# fpc.net
KiCad netlist of a schematic drawn in Altium Designer
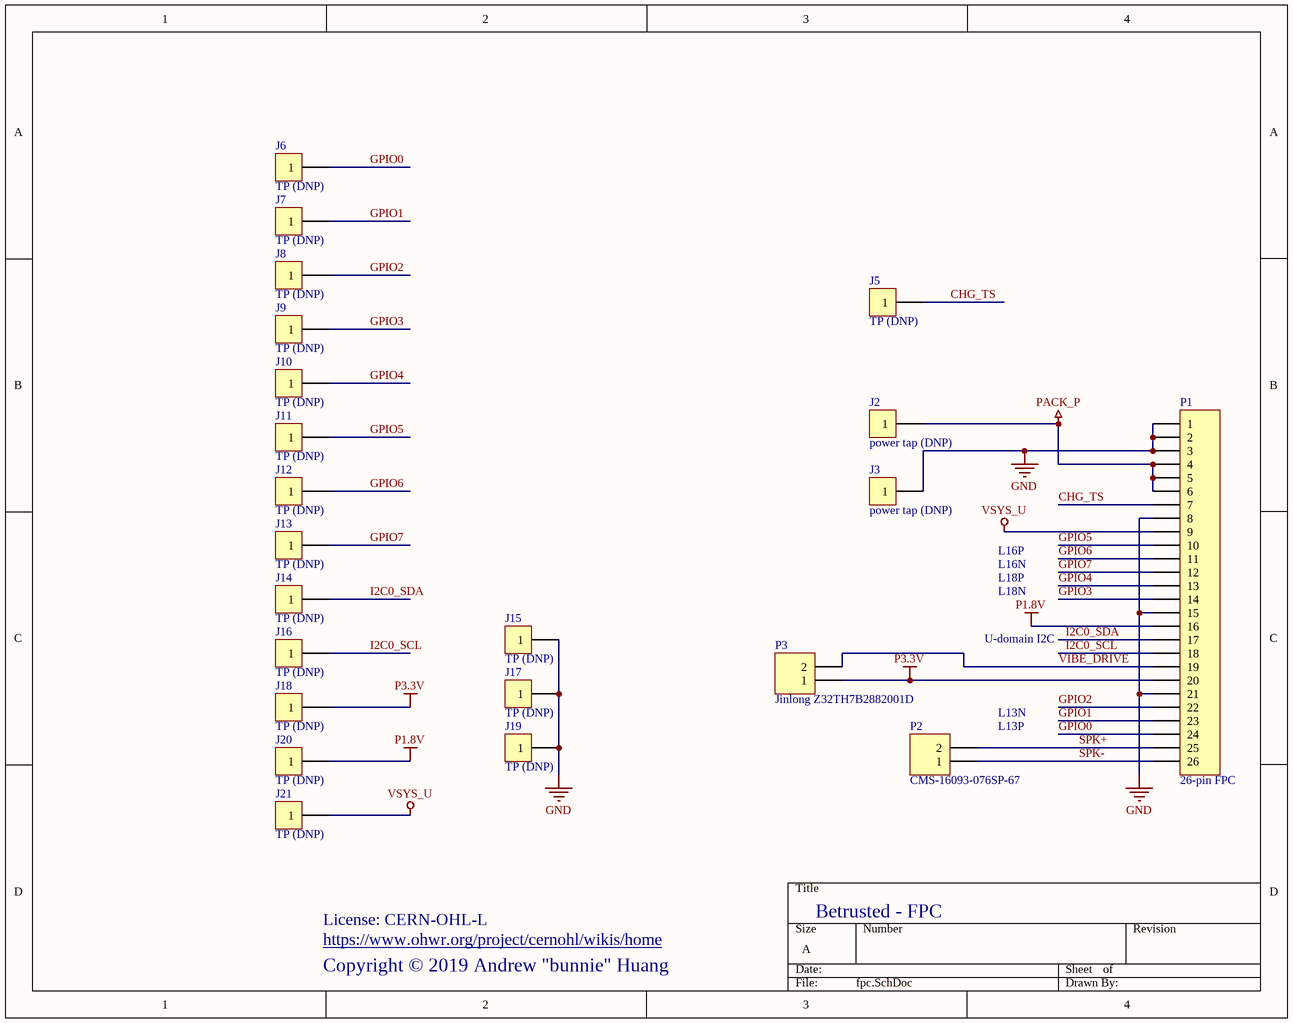
[diagram p0: fpc.SchDoc]

(export (version "E")
  (design (tool "Eeschema 10.0.6"))
  (components
    (comp (ref "J2")
      (value "power tap (DNP)")
      (footprint "RESTAP-0603")
      (description "Connector")
      (fields (field (name "MPN") "DNP"))
      (libsource (lib "*") (part "CON1"))
    )
    (comp (ref "J3")
      (value "power tap (DNP)")
      (footprint "RESTAP-0603")
      (description "Connector")
      (fields (field (name "MPN") "DNP"))
      (libsource (lib "*") (part "CON1"))
    )
    (comp (ref "J5")
      (value "TP (DNP)")
      (footprint "TP_1.5x1_SMT")
      (description "Connector")
      (fields (field (name "MPN") "DNP"))
      (libsource (lib "*") (part "CON1"))
    )
    (comp (ref "J6")
      (value "TP (DNP)")
      (footprint "TP_1.5x1_SMT")
      (description "Connector")
      (fields (field (name "MPN") "DNP"))
      (libsource (lib "*") (part "CON1"))
    )
    (comp (ref "J7")
      (value "TP (DNP)")
      (footprint "TP_1.5x1_SMT")
      (description "Connector")
      (fields (field (name "MPN") "DNP"))
      (libsource (lib "*") (part "CON1"))
    )
    (comp (ref "J8")
      (value "TP (DNP)")
      (footprint "TP_1.5x1_SMT")
      (description "Connector")
      (fields (field (name "MPN") "DNP"))
      (libsource (lib "*") (part "CON1"))
    )
    (comp (ref "J9")
      (value "TP (DNP)")
      (footprint "TP_1.5x1_SMT")
      (description "Connector")
      (fields (field (name "MPN") "DNP"))
      (libsource (lib "*") (part "CON1"))
    )
    (comp (ref "J10")
      (value "TP (DNP)")
      (footprint "TP_1.5x1_SMT")
      (description "Connector")
      (fields (field (name "MPN") "DNP"))
      (libsource (lib "*") (part "CON1"))
    )
    (comp (ref "J11")
      (value "TP (DNP)")
      (footprint "TP_1.5x1_SMT")
      (description "Connector")
      (fields (field (name "MPN") "DNP"))
      (libsource (lib "*") (part "CON1"))
    )
    (comp (ref "J12")
      (value "TP (DNP)")
      (footprint "TP_1.5x1_SMT")
      (description "Connector")
      (fields (field (name "MPN") "DNP"))
      (libsource (lib "*") (part "CON1"))
    )
    (comp (ref "J13")
      (value "TP (DNP)")
      (footprint "TP_1.5x1_SMT")
      (description "Connector")
      (fields (field (name "MPN") "DNP"))
      (libsource (lib "*") (part "CON1"))
    )
    (comp (ref "J14")
      (value "TP (DNP)")
      (footprint "TP_1.5x1_SMT")
      (description "Connector")
      (fields (field (name "MPN") "DNP"))
      (libsource (lib "*") (part "CON1"))
    )
    (comp (ref "J15")
      (value "TP (DNP)")
      (footprint "TP_1.5x1_SMT")
      (description "Connector")
      (fields (field (name "MPN") "DNP"))
      (libsource (lib "*") (part "CON1"))
    )
    (comp (ref "J16")
      (value "TP (DNP)")
      (footprint "TP_1.5x1_SMT")
      (description "Connector")
      (fields (field (name "MPN") "DNP"))
      (libsource (lib "*") (part "CON1"))
    )
    (comp (ref "J17")
      (value "TP (DNP)")
      (footprint "TP_1.5x1_SMT")
      (description "Connector")
      (fields (field (name "MPN") "DNP"))
      (libsource (lib "*") (part "CON1"))
    )
    (comp (ref "J18")
      (value "TP (DNP)")
      (footprint "TP_1.5x1_SMT")
      (description "Connector")
      (fields (field (name "MPN") "DNP"))
      (libsource (lib "*") (part "CON1"))
    )
    (comp (ref "J19")
      (value "TP (DNP)")
      (footprint "TP_1.5x1_SMT")
      (description "Connector")
      (fields (field (name "MPN") "DNP"))
      (libsource (lib "*") (part "CON1"))
    )
    (comp (ref "J20")
      (value "TP (DNP)")
      (footprint "TP_1.5x1_SMT")
      (description "Connector")
      (fields (field (name "MPN") "DNP"))
      (libsource (lib "*") (part "CON1"))
    )
    (comp (ref "J21")
      (value "TP (DNP)")
      (footprint "TP_1.5x1_SMT")
      (description "Connector")
      (fields (field (name "MPN") "DNP"))
      (libsource (lib "*") (part "CON1"))
    )
    (comp (ref "P1")
      (value "26-pin FPC")
      (footprint "HRS_FH34SRJ-26S-FPC-TOP")
      (description "26 Pin FPC footprint")
      (fields (field (name "MPN") "DNP"))
      (libsource (lib "commonsch-new") (part "FPC-26"))
    )
    (comp (ref "P2")
      (value "CMS-16093-076SP-67")
      (footprint "CUI_CMS-16093-076SP-67")
      (fields (field (name "PUBLISHER") "Altium Limited"))
      (libsource (lib "Miscellaneous Connectors") (part "Header 2"))
    )
    (comp (ref "P3")
      (value "Jinlong Z32TH7B2882001D")
      (footprint "JINLONG_Z32TH7B2882001D")
      (fields (field (name "MPN") "Z32TH7B2882001D") (field (name "PUBLISHER") "Altium Limited"))
      (libsource (lib "Miscellaneous Connectors") (part "Header 2"))
    )
  )
  (nets
    (net (code "1") (name "/CHG_TS") (class "Default")
      (node (ref "J5") (pin "1") (pinfunction "1_1") (pintype "passive"))
      (node (ref "P1") (pin "7") (pinfunction "7_7") (pintype "passive"))
    )
    (net (code "2") (name "/GPIO0") (class "Default")
      (node (ref "J6") (pin "1") (pinfunction "1_1") (pintype "passive"))
      (node (ref "P1") (pin "24") (pinfunction "24_24") (pintype "passive"))
    )
    (net (code "3") (name "/GPIO1") (class "Default")
      (node (ref "J7") (pin "1") (pinfunction "1_1") (pintype "passive"))
      (node (ref "P1") (pin "23") (pinfunction "23_23") (pintype "passive"))
    )
    (net (code "4") (name "/GPIO2") (class "Default")
      (node (ref "J8") (pin "1") (pinfunction "1_1") (pintype "passive"))
      (node (ref "P1") (pin "22") (pinfunction "22_22") (pintype "passive"))
    )
    (net (code "5") (name "/GPIO3") (class "Default")
      (node (ref "J9") (pin "1") (pinfunction "1_1") (pintype "passive"))
      (node (ref "P1") (pin "14") (pinfunction "14_14") (pintype "passive"))
    )
    (net (code "6") (name "/GPIO4") (class "Default")
      (node (ref "J10") (pin "1") (pinfunction "1_1") (pintype "passive"))
      (node (ref "P1") (pin "13") (pinfunction "13_13") (pintype "passive"))
    )
    (net (code "7") (name "/GPIO5") (class "Default")
      (node (ref "J11") (pin "1") (pinfunction "1_1") (pintype "passive"))
      (node (ref "P1") (pin "10") (pinfunction "10_10") (pintype "passive"))
    )
    (net (code "8") (name "/GPIO6") (class "Default")
      (node (ref "J12") (pin "1") (pinfunction "1_1") (pintype "passive"))
      (node (ref "P1") (pin "11") (pinfunction "11_11") (pintype "passive"))
    )
    (net (code "9") (name "/GPIO7") (class "Default")
      (node (ref "J13") (pin "1") (pinfunction "1_1") (pintype "passive"))
      (node (ref "P1") (pin "12") (pinfunction "12_12") (pintype "passive"))
    )
    (net (code "10") (name "/I2C0_SCL") (class "Default")
      (node (ref "J16") (pin "1") (pinfunction "1_1") (pintype "passive"))
      (node (ref "P1") (pin "18") (pinfunction "18_18") (pintype "passive"))
    )
    (net (code "11") (name "/I2C0_SDA") (class "Default")
      (node (ref "J14") (pin "1") (pinfunction "1_1") (pintype "passive"))
      (node (ref "P1") (pin "17") (pinfunction "17_17") (pintype "passive"))
    )
    (net (code "12") (name "/SPK+") (class "Default")
      (node (ref "P1") (pin "25") (pinfunction "25_25") (pintype "passive"))
      (node (ref "P2") (pin "2") (pinfunction "2_2") (pintype "passive"))
    )
    (net (code "13") (name "/SPK-") (class "Default")
      (node (ref "P1") (pin "26") (pinfunction "26_26") (pintype "passive"))
      (node (ref "P2") (pin "1") (pinfunction "1_1") (pintype "passive"))
    )
    (net (code "14") (name "/VIBE_DRIVE") (class "Default")
      (node (ref "P1") (pin "19") (pinfunction "19_19") (pintype "passive"))
      (node (ref "P3") (pin "2") (pinfunction "2_2") (pintype "passive"))
    )
    (net (code "15") (name "GND") (class "Default")
      (node (ref "J15") (pin "1") (pinfunction "1_1") (pintype "passive"))
      (node (ref "J17") (pin "1") (pinfunction "1_1") (pintype "passive"))
      (node (ref "J19") (pin "1") (pinfunction "1_1") (pintype "passive"))
      (node (ref "J3") (pin "1") (pinfunction "1_1") (pintype "passive"))
      (node (ref "P1") (pin "1") (pinfunction "1_1") (pintype "passive"))
      (node (ref "P1") (pin "15") (pinfunction "15_15") (pintype "passive"))
      (node (ref "P1") (pin "2") (pinfunction "2_2") (pintype "passive"))
      (node (ref "P1") (pin "21") (pinfunction "21_21") (pintype "passive"))
      (node (ref "P1") (pin "3") (pinfunction "3_3") (pintype "passive"))
      (node (ref "P1") (pin "8") (pinfunction "8_8") (pintype "passive"))
    )
    (net (code "16") (name "P1.8V") (class "Default")
      (node (ref "J20") (pin "1") (pinfunction "1_1") (pintype "passive"))
      (node (ref "P1") (pin "16") (pinfunction "16_16") (pintype "passive"))
    )
    (net (code "17") (name "P3.3V") (class "Default")
      (node (ref "J18") (pin "1") (pinfunction "1_1") (pintype "passive"))
      (node (ref "P1") (pin "20") (pinfunction "20_20") (pintype "passive"))
      (node (ref "P3") (pin "1") (pinfunction "1_1") (pintype "passive"))
    )
    (net (code "18") (name "PACK_P") (class "Default")
      (node (ref "J2") (pin "1") (pinfunction "1_1") (pintype "passive"))
      (node (ref "P1") (pin "4") (pinfunction "4_4") (pintype "passive"))
      (node (ref "P1") (pin "5") (pinfunction "5_5") (pintype "passive"))
      (node (ref "P1") (pin "6") (pinfunction "6_6") (pintype "passive"))
    )
    (net (code "19") (name "VSYS_U") (class "Default")
      (node (ref "J21") (pin "1") (pinfunction "1_1") (pintype "passive"))
      (node (ref "P1") (pin "9") (pinfunction "9_9") (pintype "passive"))
    )
  )
)
